# ClockBoard.net
KiCad netlist of a schematic drawn in EAGLE
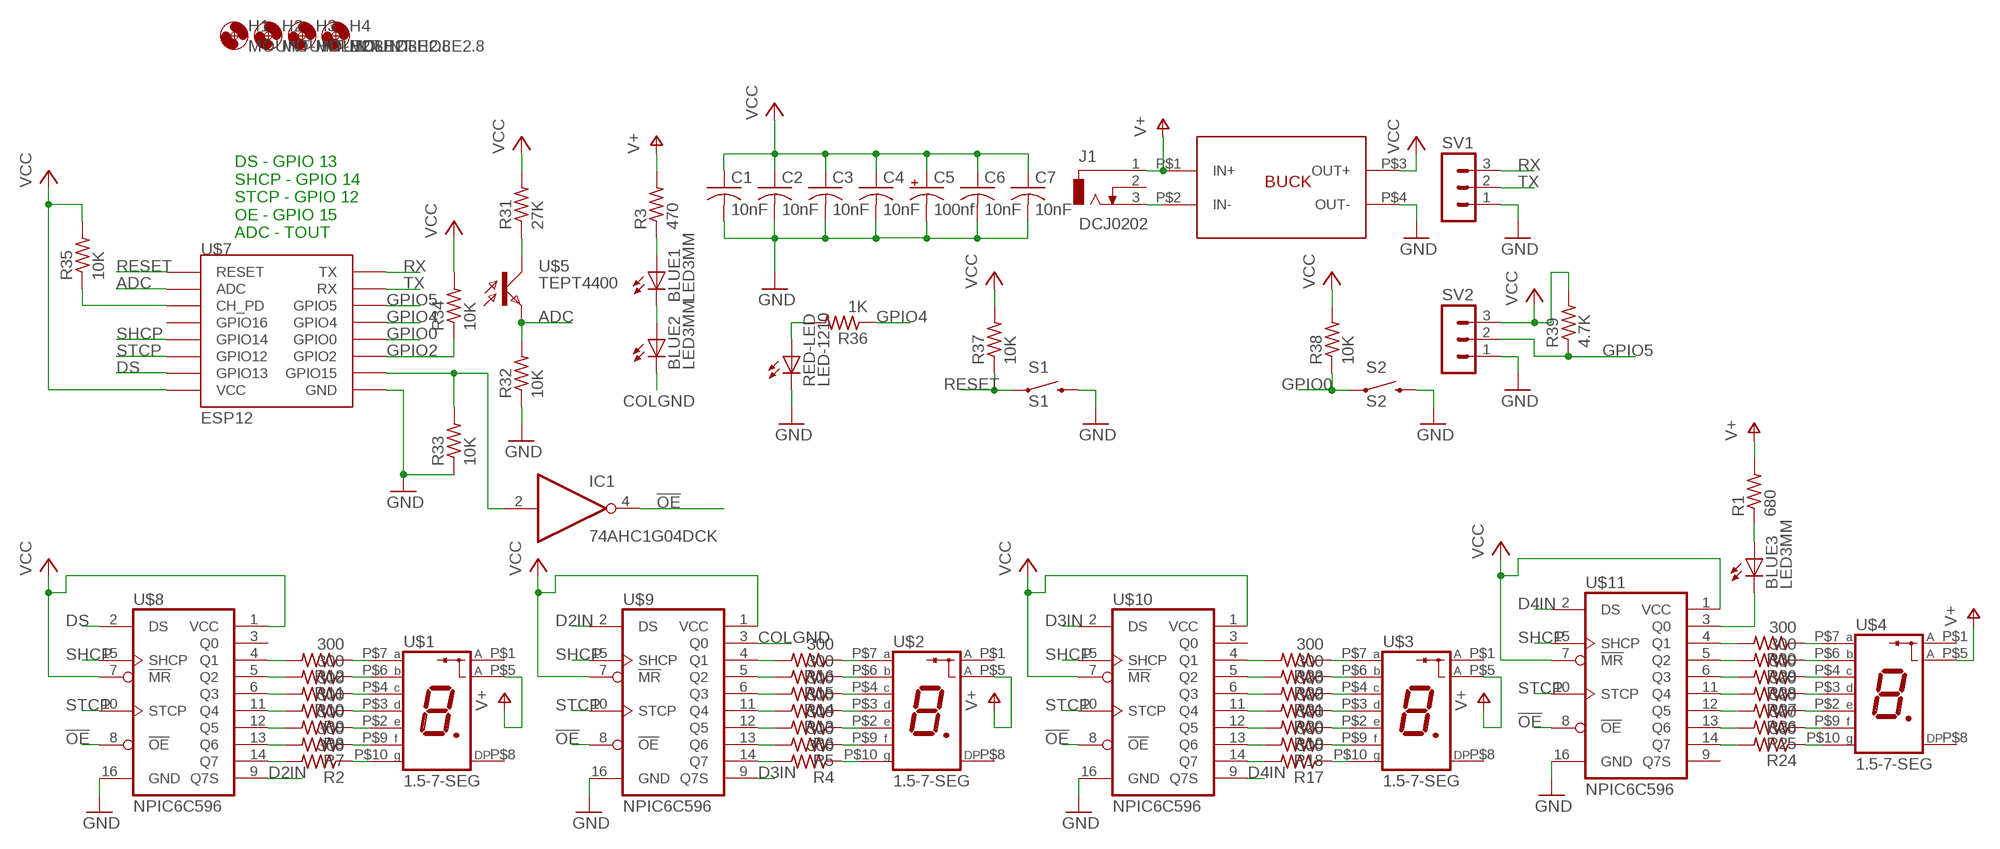
[diagram p0: schematic, sheet 1]

(export (version "E")
  (design (tool "Eeschema 10.0.6"))
  (components
    (comp (ref "B1")
      (value "BUCK_CONV")
      (footprint "eagle-import:BUCK_CONV")
      (libsource (lib "eagle-import") (part "BUCK_CONV"))
    )
    (comp (ref "BLUE1")
      (value "LED3MM")
      (footprint "eagle-import:LED3MM")
      (libsource (lib "eagle-import") (part "LED3MM"))
    )
    (comp (ref "BLUE2")
      (value "LED3MM")
      (footprint "eagle-import:LED3MM")
      (libsource (lib "eagle-import") (part "LED3MM"))
    )
    (comp (ref "BLUE3")
      (value "LED3MM")
      (footprint "eagle-import:LED3MM")
      (libsource (lib "eagle-import") (part "LED3MM"))
    )
    (comp (ref "C1")
      (value "10nF")
      (footprint "eagle-import:C0805K")
      (libsource (lib "eagle-import") (part "C-USC0805K"))
    )
    (comp (ref "C2")
      (value "10nF")
      (footprint "eagle-import:C0805K")
      (libsource (lib "eagle-import") (part "C-USC0805K"))
    )
    (comp (ref "C3")
      (value "10nF")
      (footprint "eagle-import:C0805K")
      (libsource (lib "eagle-import") (part "C-USC0805K"))
    )
    (comp (ref "C4")
      (value "10nF")
      (footprint "eagle-import:C0805K")
      (libsource (lib "eagle-import") (part "C-USC0805K"))
    )
    (comp (ref "C5")
      (value "100nf")
      (footprint "eagle-import:E5-4")
      (libsource (lib "eagle-import") (part "CPOL-USE5-4"))
    )
    (comp (ref "C6")
      (value "10nF")
      (footprint "eagle-import:C050-025X075")
      (libsource (lib "eagle-import") (part "C-US050-025X075"))
    )
    (comp (ref "C7")
      (value "10nF")
      (footprint "eagle-import:C0805K")
      (libsource (lib "eagle-import") (part "C-USC0805K"))
    )
    (comp (ref "H1")
      (value "MOUNT-HOLE2.8")
      (footprint "eagle-import:2,8")
      (libsource (lib "eagle-import") (part "MOUNT-HOLE2.8"))
    )
    (comp (ref "H2")
      (value "MOUNT-HOLE2.8")
      (footprint "eagle-import:2,8")
      (libsource (lib "eagle-import") (part "MOUNT-HOLE2.8"))
    )
    (comp (ref "H3")
      (value "MOUNT-HOLE2.8")
      (footprint "eagle-import:2,8")
      (libsource (lib "eagle-import") (part "MOUNT-HOLE2.8"))
    )
    (comp (ref "H4")
      (value "MOUNT-HOLE2.8")
      (footprint "eagle-import:2,8")
      (libsource (lib "eagle-import") (part "MOUNT-HOLE2.8"))
    )
    (comp (ref "IC1")
      (value "74AHC1G04DCK")
      (footprint "eagle-import:SC70-5")
      (libsource (lib "eagle-import") (part "741G04DCKAHC"))
    )
    (comp (ref "J1")
      (value "DCJ0202")
      (footprint "eagle-import:DCJ0202")
      (libsource (lib "eagle-import") (part "DCJ0202"))
    )
    (comp (ref "R1")
      (value "680")
      (footprint "eagle-import:M0805")
      (libsource (lib "eagle-import") (part "R-US_M0805"))
    )
    (comp (ref "R2")
      (value "300")
      (footprint "eagle-import:M0805")
      (libsource (lib "eagle-import") (part "R-US_M0805"))
    )
    (comp (ref "R3")
      (value "470")
      (footprint "eagle-import:M0805")
      (libsource (lib "eagle-import") (part "R-US_M0805"))
    )
    (comp (ref "R4")
      (value "300")
      (footprint "eagle-import:M0805")
      (libsource (lib "eagle-import") (part "R-US_M0805"))
    )
    (comp (ref "R5")
      (value "300")
      (footprint "eagle-import:M0805")
      (libsource (lib "eagle-import") (part "R-US_M0805"))
    )
    (comp (ref "R6")
      (value "300")
      (footprint "eagle-import:M0805")
      (libsource (lib "eagle-import") (part "R-US_M0805"))
    )
    (comp (ref "R7")
      (value "300")
      (footprint "eagle-import:M0805")
      (libsource (lib "eagle-import") (part "R-US_M0805"))
    )
    (comp (ref "R8")
      (value "300")
      (footprint "eagle-import:M0805")
      (libsource (lib "eagle-import") (part "R-US_M0805"))
    )
    (comp (ref "R9")
      (value "300")
      (footprint "eagle-import:M0805")
      (libsource (lib "eagle-import") (part "R-US_M0805"))
    )
    (comp (ref "R10")
      (value "300")
      (footprint "eagle-import:M0805")
      (libsource (lib "eagle-import") (part "R-US_M0805"))
    )
    (comp (ref "R11")
      (value "300")
      (footprint "eagle-import:M0805")
      (libsource (lib "eagle-import") (part "R-US_M0805"))
    )
    (comp (ref "R12")
      (value "300")
      (footprint "eagle-import:M0805")
      (libsource (lib "eagle-import") (part "R-US_M0805"))
    )
    (comp (ref "R13")
      (value "300")
      (footprint "eagle-import:M0805")
      (libsource (lib "eagle-import") (part "R-US_M0805"))
    )
    (comp (ref "R14")
      (value "300")
      (footprint "eagle-import:M0805")
      (libsource (lib "eagle-import") (part "R-US_M0805"))
    )
    (comp (ref "R15")
      (value "300")
      (footprint "eagle-import:M0805")
      (libsource (lib "eagle-import") (part "R-US_M0805"))
    )
    (comp (ref "R16")
      (value "300")
      (footprint "eagle-import:M0805")
      (libsource (lib "eagle-import") (part "R-US_M0805"))
    )
    (comp (ref "R17")
      (value "300")
      (footprint "eagle-import:M0805")
      (libsource (lib "eagle-import") (part "R-US_M0805"))
    )
    (comp (ref "R18")
      (value "300")
      (footprint "eagle-import:M0805")
      (libsource (lib "eagle-import") (part "R-US_M0805"))
    )
    (comp (ref "R19")
      (value "300")
      (footprint "eagle-import:M0805")
      (libsource (lib "eagle-import") (part "R-US_M0805"))
    )
    (comp (ref "R20")
      (value "300")
      (footprint "eagle-import:M0805")
      (libsource (lib "eagle-import") (part "R-US_M0805"))
    )
    (comp (ref "R21")
      (value "300")
      (footprint "eagle-import:M0805")
      (libsource (lib "eagle-import") (part "R-US_M0805"))
    )
    (comp (ref "R22")
      (value "300")
      (footprint "eagle-import:M0805")
      (libsource (lib "eagle-import") (part "R-US_M0805"))
    )
    (comp (ref "R23")
      (value "300")
      (footprint "eagle-import:M0805")
      (libsource (lib "eagle-import") (part "R-US_M0805"))
    )
    (comp (ref "R24")
      (value "300")
      (footprint "eagle-import:M0805")
      (libsource (lib "eagle-import") (part "R-US_M0805"))
    )
    (comp (ref "R25")
      (value "300")
      (footprint "eagle-import:M0805")
      (libsource (lib "eagle-import") (part "R-US_M0805"))
    )
    (comp (ref "R26")
      (value "300")
      (footprint "eagle-import:M0805")
      (libsource (lib "eagle-import") (part "R-US_M0805"))
    )
    (comp (ref "R27")
      (value "300")
      (footprint "eagle-import:M0805")
      (libsource (lib "eagle-import") (part "R-US_M0805"))
    )
    (comp (ref "R28")
      (value "300")
      (footprint "eagle-import:M0805")
      (libsource (lib "eagle-import") (part "R-US_M0805"))
    )
    (comp (ref "R29")
      (value "300")
      (footprint "eagle-import:M0805")
      (libsource (lib "eagle-import") (part "R-US_M0805"))
    )
    (comp (ref "R30")
      (value "300")
      (footprint "eagle-import:M0805")
      (libsource (lib "eagle-import") (part "R-US_M0805"))
    )
    (comp (ref "R31")
      (value "27K")
      (footprint "eagle-import:M0805")
      (libsource (lib "eagle-import") (part "R-US_M0805"))
    )
    (comp (ref "R32")
      (value "10K")
      (footprint "eagle-import:M0805")
      (libsource (lib "eagle-import") (part "R-US_M0805"))
    )
    (comp (ref "R33")
      (value "10K")
      (footprint "eagle-import:M0805")
      (libsource (lib "eagle-import") (part "R-US_M0805"))
    )
    (comp (ref "R34")
      (value "10K")
      (footprint "eagle-import:M0805")
      (libsource (lib "eagle-import") (part "R-US_M0805"))
    )
    (comp (ref "R35")
      (value "10K")
      (footprint "eagle-import:M0805")
      (libsource (lib "eagle-import") (part "R-US_M0805"))
    )
    (comp (ref "R36")
      (value "1K")
      (footprint "eagle-import:M0805")
      (libsource (lib "eagle-import") (part "R-US_M0805"))
    )
    (comp (ref "R37")
      (value "10K")
      (footprint "eagle-import:M0805")
      (libsource (lib "eagle-import") (part "R-US_M0805"))
    )
    (comp (ref "R38")
      (value "10K")
      (footprint "eagle-import:M0805")
      (libsource (lib "eagle-import") (part "R-US_M0805"))
    )
    (comp (ref "R39")
      (value "4.7K")
      (footprint "eagle-import:M0805")
      (libsource (lib "eagle-import") (part "R-US_M0805"))
    )
    (comp (ref "RED-LED")
      (value "LED-1210")
      (footprint "eagle-import:C1210K")
      (libsource (lib "eagle-import") (part "LED-1210"))
    )
    (comp (ref "S1")
      (value "S1")
      (footprint "eagle-import:TACTILE-PTH")
      (libsource (lib "eagle-import") (part "SWITCH-MOMENTARY-2PTH"))
    )
    (comp (ref "S2")
      (value "S2")
      (footprint "eagle-import:TACTILE-PTH")
      (libsource (lib "eagle-import") (part "SWITCH-MOMENTARY-2PTH"))
    )
    (comp (ref "SV1")
      (value "MA03-1")
      (footprint "eagle-import:MA03-1")
      (libsource (lib "eagle-import") (part "MA03-1"))
    )
    (comp (ref "SV2")
      (value "MA03-1")
      (footprint "eagle-import:MA03-1")
      (libsource (lib "eagle-import") (part "MA03-1"))
    )
    (comp (ref "U$1")
      (value "1.5-7-SEG")
      (footprint "eagle-import:1.5-7-SEG")
      (libsource (lib "eagle-import") (part "1.5-7-SEG"))
    )
    (comp (ref "U$2")
      (value "1.5-7-SEG")
      (footprint "eagle-import:1.5-7-SEG")
      (libsource (lib "eagle-import") (part "1.5-7-SEG"))
    )
    (comp (ref "U$3")
      (value "1.5-7-SEG")
      (footprint "eagle-import:1.5-7-SEG")
      (libsource (lib "eagle-import") (part "1.5-7-SEG"))
    )
    (comp (ref "U$4")
      (value "1.5-7-SEG")
      (footprint "eagle-import:1.5-7-SEG")
      (libsource (lib "eagle-import") (part "1.5-7-SEG"))
    )
    (comp (ref "U$5")
      (value "TEPT4400")
      (footprint "eagle-import:T1")
      (libsource (lib "eagle-import") (part "TEPT4400"))
    )
    (comp (ref "U$7")
      (value "ESP12")
      (footprint "eagle-import:ESP12")
      (libsource (lib "eagle-import") (part "ESP12"))
    )
    (comp (ref "U$8")
      (value "NPIC6C596")
      (footprint "eagle-import:SO16")
      (libsource (lib "eagle-import") (part "NPIC6C596"))
    )
    (comp (ref "U$9")
      (value "NPIC6C596")
      (footprint "eagle-import:SO16")
      (libsource (lib "eagle-import") (part "NPIC6C596"))
    )
    (comp (ref "U$10")
      (value "NPIC6C596")
      (footprint "eagle-import:SO16")
      (libsource (lib "eagle-import") (part "NPIC6C596"))
    )
    (comp (ref "U$11")
      (value "NPIC6C596")
      (footprint "eagle-import:SO16")
      (libsource (lib "eagle-import") (part "NPIC6C596"))
    )
  )
  (nets
    (net (code "1") (name "/ADC") (class "Default")
      (node (ref "R32") (pin "2") (pinfunction "2_2") (pintype "passive"))
      (node (ref "U$5") (pin "A") (pinfunction "E_A") (pintype "passive"))
      (node (ref "U$7") (pin "ADC") (pinfunction "ADC_ADC") (pintype "bidirectional"))
    )
    (net (code "2") (name "/COLGND") (class "Default")
      (node (ref "BLUE2") (pin "K") (pinfunction "C_K") (pintype "passive"))
      (node (ref "U$9") (pin "3") (pinfunction "Q0_3") (pintype "tri_state"))
    )
    (net (code "3") (name "/D2IN") (class "Default")
      (node (ref "U$8") (pin "9") (pinfunction "Q7S_9") (pintype "tri_state"))
      (node (ref "U$9") (pin "2") (pinfunction "DS_2") (pintype "input"))
    )
    (net (code "4") (name "/D3IN") (class "Default")
      (node (ref "U$10") (pin "2") (pinfunction "DS_2") (pintype "input"))
      (node (ref "U$9") (pin "9") (pinfunction "Q7S_9") (pintype "tri_state"))
    )
    (net (code "5") (name "/D4IN") (class "Default")
      (node (ref "U$10") (pin "9") (pinfunction "Q7S_9") (pintype "tri_state"))
      (node (ref "U$11") (pin "2") (pinfunction "DS_2") (pintype "input"))
    )
    (net (code "6") (name "/DS") (class "Default")
      (node (ref "U$7") (pin "GPIO13") (pinfunction "GPIO13_GPIO13") (pintype "bidirectional"))
      (node (ref "U$8") (pin "2") (pinfunction "DS_2") (pintype "input"))
    )
    (net (code "7") (name "/GPIO0") (class "Default")
      (node (ref "R38") (pin "1") (pinfunction "1_1") (pintype "passive"))
      (node (ref "S2") (pin "1") (pinfunction "1_1") (pintype "passive"))
      (node (ref "U$7") (pin "GPIO0") (pinfunction "GPIO0_GPIO0") (pintype "bidirectional"))
    )
    (net (code "8") (name "/GPIO2") (class "Default")
      (node (ref "R34") (pin "1") (pinfunction "1_1") (pintype "passive"))
      (node (ref "U$7") (pin "GPIO2") (pinfunction "GPIO2_GPIO2") (pintype "bidirectional"))
    )
    (net (code "9") (name "/GPIO4") (class "Default")
      (node (ref "R36") (pin "1") (pinfunction "1_1") (pintype "passive"))
      (node (ref "U$7") (pin "GPIO4") (pinfunction "GPIO4_GPIO4") (pintype "bidirectional"))
    )
    (net (code "10") (name "/GPIO5") (class "Default")
      (node (ref "R39") (pin "1") (pinfunction "1_1") (pintype "passive"))
      (node (ref "SV2") (pin "2") (pinfunction "2_2") (pintype "passive"))
      (node (ref "U$7") (pin "GPIO5") (pinfunction "GPIO5_GPIO5") (pintype "bidirectional"))
    )
    (net (code "11") (name "/RESET") (class "Default")
      (node (ref "R37") (pin "1") (pinfunction "1_1") (pintype "passive"))
      (node (ref "S1") (pin "1") (pinfunction "1_1") (pintype "passive"))
      (node (ref "U$7") (pin "RESET") (pinfunction "RESET_RESET") (pintype "bidirectional"))
    )
    (net (code "12") (name "/RX") (class "Default")
      (node (ref "SV1") (pin "3") (pinfunction "3_3") (pintype "passive"))
      (node (ref "U$7") (pin "TX") (pinfunction "TX_TX") (pintype "bidirectional"))
    )
    (net (code "13") (name "/SHCP") (class "Default")
      (node (ref "U$10") (pin "15") (pinfunction "SHCP_15") (pintype "input"))
      (node (ref "U$11") (pin "15") (pinfunction "SHCP_15") (pintype "input"))
      (node (ref "U$7") (pin "GPIO14") (pinfunction "GPIO14_GPIO14") (pintype "bidirectional"))
      (node (ref "U$8") (pin "15") (pinfunction "SHCP_15") (pintype "input"))
      (node (ref "U$9") (pin "15") (pinfunction "SHCP_15") (pintype "input"))
    )
    (net (code "14") (name "/STCP") (class "Default")
      (node (ref "U$10") (pin "10") (pinfunction "STCP_10") (pintype "input"))
      (node (ref "U$11") (pin "10") (pinfunction "STCP_10") (pintype "input"))
      (node (ref "U$7") (pin "GPIO12") (pinfunction "GPIO12_GPIO12") (pintype "bidirectional"))
      (node (ref "U$8") (pin "10") (pinfunction "STCP_10") (pintype "input"))
      (node (ref "U$9") (pin "10") (pinfunction "STCP_10") (pintype "input"))
    )
    (net (code "15") (name "/TX") (class "Default")
      (node (ref "SV1") (pin "2") (pinfunction "2_2") (pintype "passive"))
      (node (ref "U$7") (pin "RX") (pinfunction "RX_RX") (pintype "bidirectional"))
    )
    (net (code "16") (name "/~{OE}") (class "Default")
      (node (ref "IC1") (pin "4") (pinfunction "O_4") (pintype "output"))
      (node (ref "U$10") (pin "8") (pinfunction "~{OE}_8") (pintype "input"))
      (node (ref "U$11") (pin "8") (pinfunction "~{OE}_8") (pintype "input"))
      (node (ref "U$8") (pin "8") (pinfunction "~{OE}_8") (pintype "input"))
      (node (ref "U$9") (pin "8") (pinfunction "~{OE}_8") (pintype "input"))
    )
    (net (code "17") (name "GND") (class "Default")
      (node (ref "B1") (pin "P$4") (pinfunction "OUT-_P$4") (pintype "bidirectional"))
      (node (ref "C1") (pin "2") (pinfunction "2_2") (pintype "passive"))
      (node (ref "C2") (pin "2") (pinfunction "2_2") (pintype "passive"))
      (node (ref "C3") (pin "2") (pinfunction "2_2") (pintype "passive"))
      (node (ref "C4") (pin "2") (pinfunction "2_2") (pintype "passive"))
      (node (ref "C5") (pin "-") (pinfunction "-_-") (pintype "passive"))
      (node (ref "C6") (pin "2") (pinfunction "2_2") (pintype "passive"))
      (node (ref "C7") (pin "2") (pinfunction "2_2") (pintype "passive"))
      (node (ref "R32") (pin "1") (pinfunction "1_1") (pintype "passive"))
      (node (ref "R33") (pin "1") (pinfunction "1_1") (pintype "passive"))
      (node (ref "RED-LED") (pin "2") (pinfunction "C_2") (pintype "passive"))
      (node (ref "S1") (pin "3") (pinfunction "2_3") (pintype "passive"))
      (node (ref "S2") (pin "3") (pinfunction "2_3") (pintype "passive"))
      (node (ref "SV1") (pin "1") (pinfunction "1_1") (pintype "passive"))
      (node (ref "SV2") (pin "1") (pinfunction "1_1") (pintype "passive"))
      (node (ref "U$10") (pin "16") (pinfunction "GND_16") (pintype "power_in"))
      (node (ref "U$11") (pin "16") (pinfunction "GND_16") (pintype "power_in"))
      (node (ref "U$7") (pin "GND") (pinfunction "GND_GND") (pintype "bidirectional"))
      (node (ref "U$8") (pin "16") (pinfunction "GND_16") (pintype "power_in"))
      (node (ref "U$9") (pin "16") (pinfunction "GND_16") (pintype "power_in"))
    )
    (net (code "18") (name "Net-(B1-IN-)") (class "Default")
      (node (ref "B1") (pin "P$2") (pinfunction "IN-_P$2") (pintype "bidirectional"))
      (node (ref "J1") (pin "3") (pinfunction "3_3") (pintype "passive"))
    )
    (net (code "19") (name "Net-(BLUE1-C)") (class "Default")
      (node (ref "BLUE1") (pin "K") (pinfunction "C_K") (pintype "passive"))
      (node (ref "BLUE2") (pin "A") (pinfunction "A_A") (pintype "passive"))
    )
    (net (code "20") (name "Net-(BLUE1-PadA)") (class "Default")
      (node (ref "BLUE1") (pin "A") (pinfunction "A_A") (pintype "passive"))
      (node (ref "R3") (pin "1") (pinfunction "1_1") (pintype "passive"))
    )
    (net (code "21") (name "Net-(BLUE3-C)") (class "Default")
      (node (ref "BLUE3") (pin "K") (pinfunction "C_K") (pintype "passive"))
      (node (ref "U$11") (pin "3") (pinfunction "Q0_3") (pintype "tri_state"))
    )
    (net (code "22") (name "Net-(BLUE3-PadA)") (class "Default")
      (node (ref "BLUE3") (pin "A") (pinfunction "A_A") (pintype "passive"))
      (node (ref "R1") (pin "1") (pinfunction "1_1") (pintype "passive"))
    )
    (net (code "23") (name "Net-(IC1A-I)") (class "Default")
      (node (ref "IC1") (pin "2") (pinfunction "I_2") (pintype "input"))
      (node (ref "R33") (pin "2") (pinfunction "2_2") (pintype "passive"))
      (node (ref "U$7") (pin "GPIO15") (pinfunction "GPIO15_GPIO15") (pintype "bidirectional"))
    )
    (net (code "24") (name "Net-(R12-Pad1)") (class "Default")
      (node (ref "R12") (pin "1") (pinfunction "1_1") (pintype "passive"))
      (node (ref "U$1") (pin "P$7") (pinfunction "A_P$7") (pintype "passive"))
    )
    (net (code "25") (name "Net-(R16-Pad1)") (class "Default")
      (node (ref "R16") (pin "1") (pinfunction "1_1") (pintype "passive"))
      (node (ref "U$2") (pin "P$7") (pinfunction "A_P$7") (pintype "passive"))
    )
    (net (code "26") (name "Net-(R23-Pad1)") (class "Default")
      (node (ref "R23") (pin "1") (pinfunction "1_1") (pintype "passive"))
      (node (ref "U$3") (pin "P$7") (pinfunction "A_P$7") (pintype "passive"))
    )
    (net (code "27") (name "Net-(R30-Pad1)") (class "Default")
      (node (ref "R30") (pin "1") (pinfunction "1_1") (pintype "passive"))
      (node (ref "U$4") (pin "P$7") (pinfunction "A_P$7") (pintype "passive"))
    )
    (net (code "28") (name "Net-(R35-Pad1)") (class "Default")
      (node (ref "R35") (pin "1") (pinfunction "1_1") (pintype "passive"))
      (node (ref "U$7") (pin "CH_PD") (pinfunction "CH_PD_CH_PD") (pintype "bidirectional"))
    )
    (net (code "29") (name "Net-(RED-LED-A)") (class "Default")
      (node (ref "R36") (pin "2") (pinfunction "2_2") (pintype "passive"))
      (node (ref "RED-LED") (pin "1") (pinfunction "A_1") (pintype "passive"))
    )
    (net (code "30") (name "Net-(U$1-B)") (class "Default")
      (node (ref "R11") (pin "1") (pinfunction "1_1") (pintype "passive"))
      (node (ref "U$1") (pin "P$6") (pinfunction "B_P$6") (pintype "passive"))
    )
    (net (code "31") (name "Net-(U$1-C)") (class "Default")
      (node (ref "R10") (pin "1") (pinfunction "1_1") (pintype "passive"))
      (node (ref "U$1") (pin "P$4") (pinfunction "C_P$4") (pintype "passive"))
    )
    (net (code "32") (name "Net-(U$1-D)") (class "Default")
      (node (ref "R9") (pin "1") (pinfunction "1_1") (pintype "passive"))
      (node (ref "U$1") (pin "P$3") (pinfunction "D_P$3") (pintype "passive"))
    )
    (net (code "33") (name "Net-(U$1-E)") (class "Default")
      (node (ref "R8") (pin "1") (pinfunction "1_1") (pintype "passive"))
      (node (ref "U$1") (pin "P$2") (pinfunction "E_P$2") (pintype "passive"))
    )
    (net (code "34") (name "Net-(U$1-F)") (class "Default")
      (node (ref "R7") (pin "1") (pinfunction "1_1") (pintype "passive"))
      (node (ref "U$1") (pin "P$9") (pinfunction "F_P$9") (pintype "passive"))
    )
    (net (code "35") (name "Net-(U$1-G)") (class "Default")
      (node (ref "R2") (pin "1") (pinfunction "1_1") (pintype "passive"))
      (node (ref "U$1") (pin "P$10") (pinfunction "G_P$10") (pintype "passive"))
    )
    (net (code "36") (name "Net-(U$2-B)") (class "Default")
      (node (ref "R15") (pin "1") (pinfunction "1_1") (pintype "passive"))
      (node (ref "U$2") (pin "P$6") (pinfunction "B_P$6") (pintype "passive"))
    )
    (net (code "37") (name "Net-(U$2-C)") (class "Default")
      (node (ref "R14") (pin "1") (pinfunction "1_1") (pintype "passive"))
      (node (ref "U$2") (pin "P$4") (pinfunction "C_P$4") (pintype "passive"))
    )
    (net (code "38") (name "Net-(U$2-D)") (class "Default")
      (node (ref "R13") (pin "1") (pinfunction "1_1") (pintype "passive"))
      (node (ref "U$2") (pin "P$3") (pinfunction "D_P$3") (pintype "passive"))
    )
    (net (code "39") (name "Net-(U$2-E)") (class "Default")
      (node (ref "R6") (pin "1") (pinfunction "1_1") (pintype "passive"))
      (node (ref "U$2") (pin "P$2") (pinfunction "E_P$2") (pintype "passive"))
    )
    (net (code "40") (name "Net-(U$2-F)") (class "Default")
      (node (ref "R5") (pin "1") (pinfunction "1_1") (pintype "passive"))
      (node (ref "U$2") (pin "P$9") (pinfunction "F_P$9") (pintype "passive"))
    )
    (net (code "41") (name "Net-(U$2-G)") (class "Default")
      (node (ref "R4") (pin "1") (pinfunction "1_1") (pintype "passive"))
      (node (ref "U$2") (pin "P$10") (pinfunction "G_P$10") (pintype "passive"))
    )
    (net (code "42") (name "Net-(U$3-B)") (class "Default")
      (node (ref "R22") (pin "1") (pinfunction "1_1") (pintype "passive"))
      (node (ref "U$3") (pin "P$6") (pinfunction "B_P$6") (pintype "passive"))
    )
    (net (code "43") (name "Net-(U$3-C)") (class "Default")
      (node (ref "R21") (pin "1") (pinfunction "1_1") (pintype "passive"))
      (node (ref "U$3") (pin "P$4") (pinfunction "C_P$4") (pintype "passive"))
    )
    (net (code "44") (name "Net-(U$3-D)") (class "Default")
      (node (ref "R20") (pin "1") (pinfunction "1_1") (pintype "passive"))
      (node (ref "U$3") (pin "P$3") (pinfunction "D_P$3") (pintype "passive"))
    )
    (net (code "45") (name "Net-(U$3-E)") (class "Default")
      (node (ref "R19") (pin "1") (pinfunction "1_1") (pintype "passive"))
      (node (ref "U$3") (pin "P$2") (pinfunction "E_P$2") (pintype "passive"))
    )
    (net (code "46") (name "Net-(U$3-F)") (class "Default")
      (node (ref "R18") (pin "1") (pinfunction "1_1") (pintype "passive"))
      (node (ref "U$3") (pin "P$9") (pinfunction "F_P$9") (pintype "passive"))
    )
    (net (code "47") (name "Net-(U$3-G)") (class "Default")
      (node (ref "R17") (pin "1") (pinfunction "1_1") (pintype "passive"))
      (node (ref "U$3") (pin "P$10") (pinfunction "G_P$10") (pintype "passive"))
    )
    (net (code "48") (name "Net-(U$4-B)") (class "Default")
      (node (ref "R29") (pin "1") (pinfunction "1_1") (pintype "passive"))
      (node (ref "U$4") (pin "P$6") (pinfunction "B_P$6") (pintype "passive"))
    )
    (net (code "49") (name "Net-(U$4-C)") (class "Default")
      (node (ref "R28") (pin "1") (pinfunction "1_1") (pintype "passive"))
      (node (ref "U$4") (pin "P$4") (pinfunction "C_P$4") (pintype "passive"))
    )
    (net (code "50") (name "Net-(U$4-D)") (class "Default")
      (node (ref "R27") (pin "1") (pinfunction "1_1") (pintype "passive"))
      (node (ref "U$4") (pin "P$3") (pinfunction "D_P$3") (pintype "passive"))
    )
    (net (code "51") (name "Net-(U$4-E)") (class "Default")
      (node (ref "R26") (pin "1") (pinfunction "1_1") (pintype "passive"))
      (node (ref "U$4") (pin "P$2") (pinfunction "E_P$2") (pintype "passive"))
    )
    (net (code "52") (name "Net-(U$4-F)") (class "Default")
      (node (ref "R25") (pin "1") (pinfunction "1_1") (pintype "passive"))
      (node (ref "U$4") (pin "P$9") (pinfunction "F_P$9") (pintype "passive"))
    )
    (net (code "53") (name "Net-(U$4-G)") (class "Default")
      (node (ref "R24") (pin "1") (pinfunction "1_1") (pintype "passive"))
      (node (ref "U$4") (pin "P$10") (pinfunction "G_P$10") (pintype "passive"))
    )
    (net (code "54") (name "Net-(U$5-C)") (class "Default")
      (node (ref "R31") (pin "1") (pinfunction "1_1") (pintype "passive"))
      (node (ref "U$5") (pin "K") (pinfunction "C_K") (pintype "passive"))
    )
    (net (code "55") (name "Net-(U$8-Q1)") (class "Default")
      (node (ref "R12") (pin "2") (pinfunction "2_2") (pintype "passive"))
      (node (ref "U$8") (pin "4") (pinfunction "Q1_4") (pintype "tri_state"))
    )
    (net (code "56") (name "Net-(U$8-Q2)") (class "Default")
      (node (ref "R11") (pin "2") (pinfunction "2_2") (pintype "passive"))
      (node (ref "U$8") (pin "5") (pinfunction "Q2_5") (pintype "tri_state"))
    )
    (net (code "57") (name "Net-(U$8-Q3)") (class "Default")
      (node (ref "R10") (pin "2") (pinfunction "2_2") (pintype "passive"))
      (node (ref "U$8") (pin "6") (pinfunction "Q3_6") (pintype "tri_state"))
    )
    (net (code "58") (name "Net-(U$8-Q4)") (class "Default")
      (node (ref "R9") (pin "2") (pinfunction "2_2") (pintype "passive"))
      (node (ref "U$8") (pin "11") (pinfunction "Q4_11") (pintype "tri_state"))
    )
    (net (code "59") (name "Net-(U$8-Q5)") (class "Default")
      (node (ref "R8") (pin "2") (pinfunction "2_2") (pintype "passive"))
      (node (ref "U$8") (pin "12") (pinfunction "Q5_12") (pintype "tri_state"))
    )
    (net (code "60") (name "Net-(U$8-Q6)") (class "Default")
      (node (ref "R7") (pin "2") (pinfunction "2_2") (pintype "passive"))
      (node (ref "U$8") (pin "13") (pinfunction "Q6_13") (pintype "tri_state"))
    )
    (net (code "61") (name "Net-(U$8-Q7)") (class "Default")
      (node (ref "R2") (pin "2") (pinfunction "2_2") (pintype "passive"))
      (node (ref "U$8") (pin "14") (pinfunction "Q7_14") (pintype "tri_state"))
    )
    (net (code "62") (name "Net-(U$9-Q1)") (class "Default")
      (node (ref "R16") (pin "2") (pinfunction "2_2") (pintype "passive"))
      (node (ref "U$9") (pin "4") (pinfunction "Q1_4") (pintype "tri_state"))
    )
    (net (code "63") (name "Net-(U$9-Q2)") (class "Default")
      (node (ref "R15") (pin "2") (pinfunction "2_2") (pintype "passive"))
      (node (ref "U$9") (pin "5") (pinfunction "Q2_5") (pintype "tri_state"))
    )
    (net (code "64") (name "Net-(U$9-Q3)") (class "Default")
      (node (ref "R14") (pin "2") (pinfunction "2_2") (pintype "passive"))
      (node (ref "U$9") (pin "6") (pinfunction "Q3_6") (pintype "tri_state"))
    )
    (net (code "65") (name "Net-(U$9-Q4)") (class "Default")
      (node (ref "R13") (pin "2") (pinfunction "2_2") (pintype "passive"))
      (node (ref "U$9") (pin "11") (pinfunction "Q4_11") (pintype "tri_state"))
    )
    (net (code "66") (name "Net-(U$9-Q5)") (class "Default")
      (node (ref "R6") (pin "2") (pinfunction "2_2") (pintype "passive"))
      (node (ref "U$9") (pin "12") (pinfunction "Q5_12") (pintype "tri_state"))
    )
    (net (code "67") (name "Net-(U$9-Q6)") (class "Default")
      (node (ref "R5") (pin "2") (pinfunction "2_2") (pintype "passive"))
      (node (ref "U$9") (pin "13") (pinfunction "Q6_13") (pintype "tri_state"))
    )
    (net (code "68") (name "Net-(U$9-Q7)") (class "Default")
      (node (ref "R4") (pin "2") (pinfunction "2_2") (pintype "passive"))
      (node (ref "U$9") (pin "14") (pinfunction "Q7_14") (pintype "tri_state"))
    )
    (net (code "69") (name "Net-(U$10-Q1)") (class "Default")
      (node (ref "R23") (pin "2") (pinfunction "2_2") (pintype "passive"))
      (node (ref "U$10") (pin "4") (pinfunction "Q1_4") (pintype "tri_state"))
    )
    (net (code "70") (name "Net-(U$10-Q2)") (class "Default")
      (node (ref "R22") (pin "2") (pinfunction "2_2") (pintype "passive"))
      (node (ref "U$10") (pin "5") (pinfunction "Q2_5") (pintype "tri_state"))
    )
    (net (code "71") (name "Net-(U$10-Q3)") (class "Default")
      (node (ref "R21") (pin "2") (pinfunction "2_2") (pintype "passive"))
      (node (ref "U$10") (pin "6") (pinfunction "Q3_6") (pintype "tri_state"))
    )
    (net (code "72") (name "Net-(U$10-Q4)") (class "Default")
      (node (ref "R20") (pin "2") (pinfunction "2_2") (pintype "passive"))
      (node (ref "U$10") (pin "11") (pinfunction "Q4_11") (pintype "tri_state"))
    )
    (net (code "73") (name "Net-(U$10-Q5)") (class "Default")
      (node (ref "R19") (pin "2") (pinfunction "2_2") (pintype "passive"))
      (node (ref "U$10") (pin "12") (pinfunction "Q5_12") (pintype "tri_state"))
    )
    (net (code "74") (name "Net-(U$10-Q6)") (class "Default")
      (node (ref "R18") (pin "2") (pinfunction "2_2") (pintype "passive"))
      (node (ref "U$10") (pin "13") (pinfunction "Q6_13") (pintype "tri_state"))
    )
    (net (code "75") (name "Net-(U$10-Q7)") (class "Default")
      (node (ref "R17") (pin "2") (pinfunction "2_2") (pintype "passive"))
      (node (ref "U$10") (pin "14") (pinfunction "Q7_14") (pintype "tri_state"))
    )
    (net (code "76") (name "Net-(U$11-Q1)") (class "Default")
      (node (ref "R30") (pin "2") (pinfunction "2_2") (pintype "passive"))
      (node (ref "U$11") (pin "4") (pinfunction "Q1_4") (pintype "tri_state"))
    )
    (net (code "77") (name "Net-(U$11-Q2)") (class "Default")
      (node (ref "R29") (pin "2") (pinfunction "2_2") (pintype "passive"))
      (node (ref "U$11") (pin "5") (pinfunction "Q2_5") (pintype "tri_state"))
    )
    (net (code "78") (name "Net-(U$11-Q3)") (class "Default")
      (node (ref "R28") (pin "2") (pinfunction "2_2") (pintype "passive"))
      (node (ref "U$11") (pin "6") (pinfunction "Q3_6") (pintype "tri_state"))
    )
    (net (code "79") (name "Net-(U$11-Q4)") (class "Default")
      (node (ref "R27") (pin "2") (pinfunction "2_2") (pintype "passive"))
      (node (ref "U$11") (pin "11") (pinfunction "Q4_11") (pintype "tri_state"))
    )
    (net (code "80") (name "Net-(U$11-Q5)") (class "Default")
      (node (ref "R26") (pin "2") (pinfunction "2_2") (pintype "passive"))
      (node (ref "U$11") (pin "12") (pinfunction "Q5_12") (pintype "tri_state"))
    )
    (net (code "81") (name "Net-(U$11-Q6)") (class "Default")
      (node (ref "R25") (pin "2") (pinfunction "2_2") (pintype "passive"))
      (node (ref "U$11") (pin "13") (pinfunction "Q6_13") (pintype "tri_state"))
    )
    (net (code "82") (name "Net-(U$11-Q7)") (class "Default")
      (node (ref "R24") (pin "2") (pinfunction "2_2") (pintype "passive"))
      (node (ref "U$11") (pin "14") (pinfunction "Q7_14") (pintype "tri_state"))
    )
    (net (code "83") (name "V+") (class "Default")
      (node (ref "B1") (pin "P$1") (pinfunction "IN+_P$1") (pintype "bidirectional"))
      (node (ref "J1") (pin "1") (pinfunction "1_1") (pintype "passive"))
      (node (ref "R1") (pin "2") (pinfunction "2_2") (pintype "passive"))
      (node (ref "R3") (pin "2") (pinfunction "2_2") (pintype "passive"))
      (node (ref "U$1") (pin "P$5") (pinfunction "A_P$5") (pintype "passive"))
      (node (ref "U$2") (pin "P$5") (pinfunction "A_P$5") (pintype "passive"))
      (node (ref "U$3") (pin "P$5") (pinfunction "A_P$5") (pintype "passive"))
      (node (ref "U$4") (pin "P$5") (pinfunction "A_P$5") (pintype "passive"))
    )
    (net (code "84") (name "VCC") (class "Default")
      (node (ref "B1") (pin "P$3") (pinfunction "OUT+_P$3") (pintype "bidirectional"))
      (node (ref "C1") (pin "1") (pinfunction "1_1") (pintype "passive"))
      (node (ref "C2") (pin "1") (pinfunction "1_1") (pintype "passive"))
      (node (ref "C3") (pin "1") (pinfunction "1_1") (pintype "passive"))
      (node (ref "C4") (pin "1") (pinfunction "1_1") (pintype "passive"))
      (node (ref "C5") (pin "+") (pinfunction "+_+") (pintype "passive"))
      (node (ref "C6") (pin "1") (pinfunction "1_1") (pintype "passive"))
      (node (ref "C7") (pin "1") (pinfunction "1_1") (pintype "passive"))
      (node (ref "R31") (pin "2") (pinfunction "2_2") (pintype "passive"))
      (node (ref "R34") (pin "2") (pinfunction "2_2") (pintype "passive"))
      (node (ref "R35") (pin "2") (pinfunction "2_2") (pintype "passive"))
      (node (ref "R37") (pin "2") (pinfunction "2_2") (pintype "passive"))
      (node (ref "R38") (pin "2") (pinfunction "2_2") (pintype "passive"))
      (node (ref "R39") (pin "2") (pinfunction "2_2") (pintype "passive"))
      (node (ref "SV2") (pin "3") (pinfunction "3_3") (pintype "passive"))
      (node (ref "U$10") (pin "1") (pinfunction "VCC_1") (pintype "power_in"))
      (node (ref "U$10") (pin "7") (pinfunction "~{MR}_7") (pintype "input"))
      (node (ref "U$11") (pin "1") (pinfunction "VCC_1") (pintype "power_in"))
      (node (ref "U$11") (pin "7") (pinfunction "~{MR}_7") (pintype "input"))
      (node (ref "U$7") (pin "VCC") (pinfunction "VCC_VCC") (pintype "bidirectional"))
      (node (ref "U$8") (pin "1") (pinfunction "VCC_1") (pintype "power_in"))
      (node (ref "U$8") (pin "7") (pinfunction "~{MR}_7") (pintype "input"))
      (node (ref "U$9") (pin "1") (pinfunction "VCC_1") (pintype "power_in"))
      (node (ref "U$9") (pin "7") (pinfunction "~{MR}_7") (pintype "input"))
    )
    (net (code "85") (name "unconnected-(J1-Pad2)") (class "Default")
      (node (ref "J1") (pin "2") (pinfunction "2_2") (pintype "passive"))
    )
    (net (code "86") (name "unconnected-(U$1-A-PadP$1)") (class "Default")
      (node (ref "U$1") (pin "P$1") (pinfunction "A_P$1") (pintype "passive"))
    )
    (net (code "87") (name "unconnected-(U$1-DP-PadP$8)") (class "Default")
      (node (ref "U$1") (pin "P$8") (pinfunction "DP_P$8") (pintype "passive"))
    )
    (net (code "88") (name "unconnected-(U$2-A-PadP$1)") (class "Default")
      (node (ref "U$2") (pin "P$1") (pinfunction "A_P$1") (pintype "passive"))
    )
    (net (code "89") (name "unconnected-(U$2-DP-PadP$8)") (class "Default")
      (node (ref "U$2") (pin "P$8") (pinfunction "DP_P$8") (pintype "passive"))
    )
    (net (code "90") (name "unconnected-(U$3-A-PadP$1)") (class "Default")
      (node (ref "U$3") (pin "P$1") (pinfunction "A_P$1") (pintype "passive"))
    )
    (net (code "91") (name "unconnected-(U$3-DP-PadP$8)") (class "Default")
      (node (ref "U$3") (pin "P$8") (pinfunction "DP_P$8") (pintype "passive"))
    )
    (net (code "92") (name "unconnected-(U$4-A-PadP$1)") (class "Default")
      (node (ref "U$4") (pin "P$1") (pinfunction "A_P$1") (pintype "passive"))
    )
    (net (code "93") (name "unconnected-(U$4-DP-PadP$8)") (class "Default")
      (node (ref "U$4") (pin "P$8") (pinfunction "DP_P$8") (pintype "passive"))
    )
    (net (code "94") (name "unconnected-(U$7-PadGPIO16)") (class "Default")
      (node (ref "U$7") (pin "GPIO16") (pinfunction "GPIO16_GPIO16") (pintype "bidirectional"))
    )
    (net (code "95") (name "unconnected-(U$8-Q0-Pad3)") (class "Default")
      (node (ref "U$8") (pin "3") (pinfunction "Q0_3") (pintype "tri_state"))
    )
    (net (code "96") (name "unconnected-(U$10-Q0-Pad3)") (class "Default")
      (node (ref "U$10") (pin "3") (pinfunction "Q0_3") (pintype "tri_state"))
    )
    (net (code "97") (name "unconnected-(U$11-Q7S-Pad9)") (class "Default")
      (node (ref "U$11") (pin "9") (pinfunction "Q7S_9") (pintype "tri_state"))
    )
  )
)
